# BLE232_main.net
KiCad netlist of a schematic drawn in Altium Designer
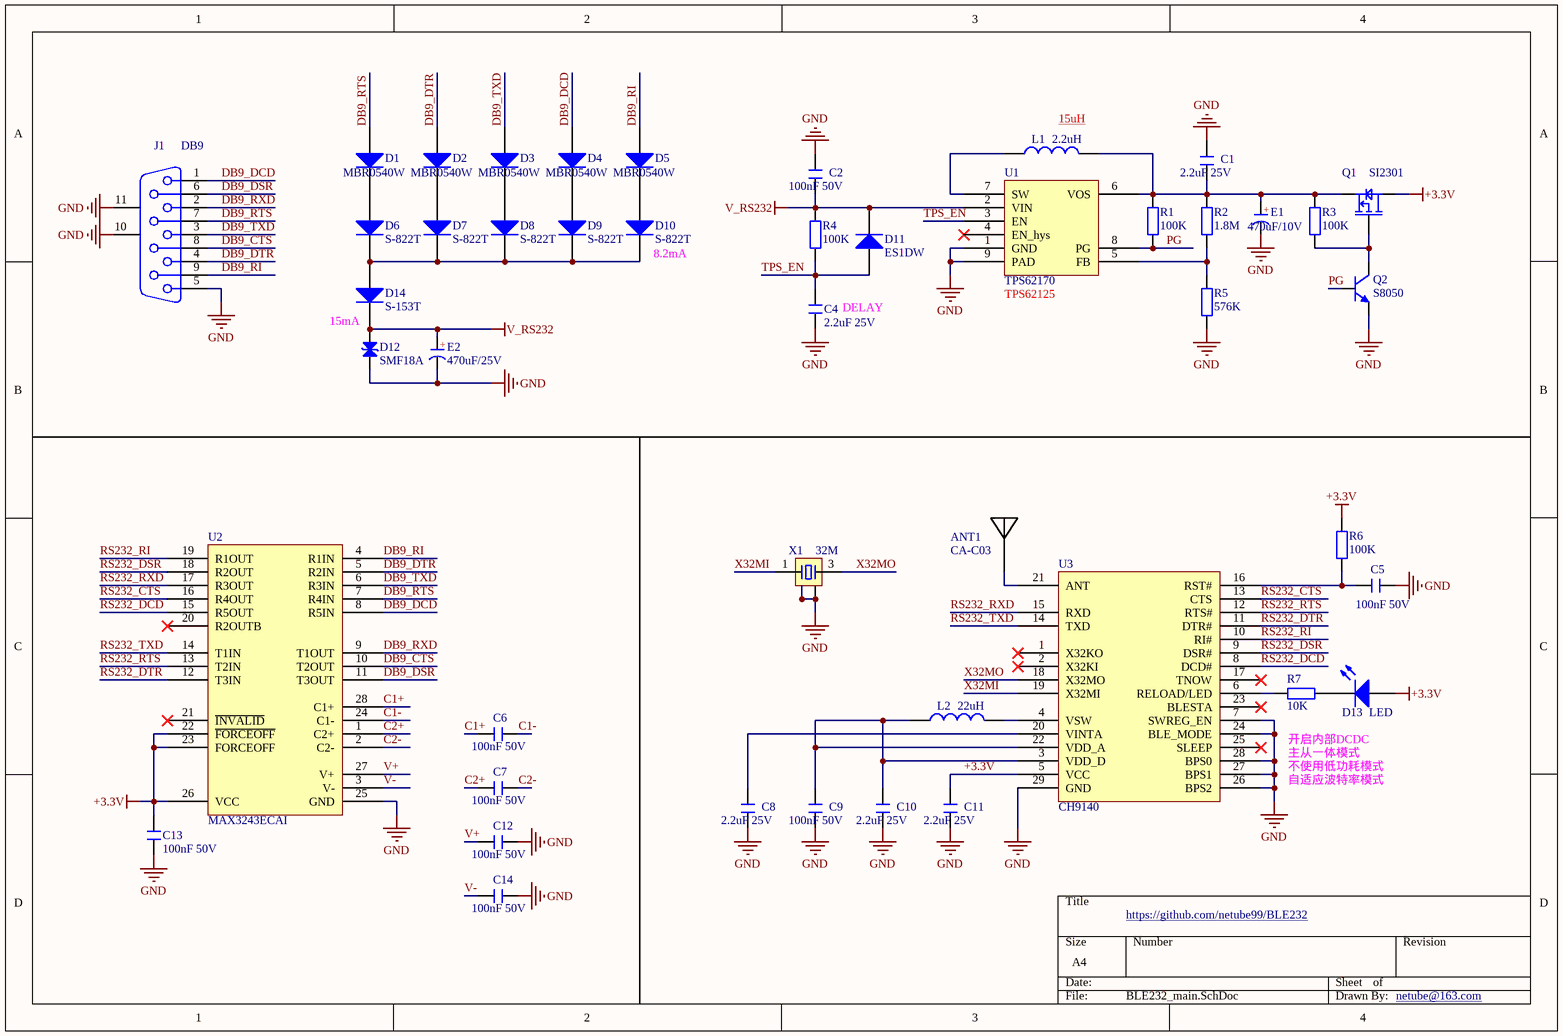
[diagram p0: BLE232_main.SchDoc]

(export (version "E")
  (design (tool "Eeschema 10.0.6"))
  (components
    (comp (ref "ANT1")
      (value "CA-C03")
      (footprint "CA-C03")
      (description "PCB板载天线")
      (fields (field (name "版权归属") "封装库来自淘宝 ID：黄晶宝石"))
      (libsource (lib "1.8 - WiFi天线-SMA射频座") (part "ANT1"))
    )
    (comp (ref "C1")
      (value "2.2uF 25V")
      (footprint "C 0603_L")
      (description "贴片电容")
      (libsource (lib "0.1 - 电阻-电容-电感") (part "C"))
    )
    (comp (ref "C2")
      (value "100nF 50V")
      (footprint "C 0603_L")
      (description "贴片电容")
      (libsource (lib "0.1 - 电阻-电容-电感") (part "C"))
    )
    (comp (ref "C4")
      (value "2.2uF 25V")
      (footprint "C 0603_L")
      (description "贴片电容")
      (libsource (lib "0.1 - 电阻-电容-电感") (part "C"))
    )
    (comp (ref "C5")
      (value "100nF 50V")
      (footprint "C 0603_L")
      (description "贴片电容")
      (libsource (lib "0.1 - 电阻-电容-电感") (part "C"))
    )
    (comp (ref "C6")
      (value "100nF 50V")
      (footprint "C 0603_L")
      (description "贴片电容")
      (libsource (lib "0.1 - 电阻-电容-电感") (part "C"))
    )
    (comp (ref "C7")
      (value "100nF 50V")
      (footprint "C 0603_L")
      (description "贴片电容")
      (libsource (lib "0.1 - 电阻-电容-电感") (part "C"))
    )
    (comp (ref "C8")
      (value "2.2uF 25V")
      (footprint "C 0603_L")
      (description "贴片电容")
      (libsource (lib "0.1 - 电阻-电容-电感") (part "C"))
    )
    (comp (ref "C9")
      (value "100nF 50V")
      (footprint "C 0603_L")
      (description "贴片电容")
      (libsource (lib "0.1 - 电阻-电容-电感") (part "C"))
    )
    (comp (ref "C10")
      (value "2.2uF 25V")
      (footprint "C 0603_L")
      (description "贴片电容")
      (libsource (lib "0.1 - 电阻-电容-电感") (part "C"))
    )
    (comp (ref "C11")
      (value "2.2uF 25V")
      (footprint "C 0603_L")
      (description "贴片电容")
      (libsource (lib "0.1 - 电阻-电容-电感") (part "C"))
    )
    (comp (ref "C12")
      (value "100nF 50V")
      (footprint "C 0603_L")
      (description "贴片电容")
      (libsource (lib "0.1 - 电阻-电容-电感") (part "C"))
    )
    (comp (ref "C13")
      (value "100nF 50V")
      (footprint "C 0603_L")
      (description "贴片电容")
      (libsource (lib "0.1 - 电阻-电容-电感") (part "C"))
    )
    (comp (ref "C14")
      (value "100nF 50V")
      (footprint "C 0603_L")
      (description "贴片电容")
      (libsource (lib "0.1 - 电阻-电容-电感") (part "C"))
    )
    (comp (ref "D1")
      (value "MBR0540W")
      (footprint "SOD-123")
      (description "二极管")
      (libsource (lib "0.2 - 二极管-整流桥") (part "Diode"))
    )
    (comp (ref "D2")
      (value "MBR0540W")
      (footprint "SOD-123")
      (description "二极管")
      (libsource (lib "0.2 - 二极管-整流桥") (part "Diode"))
    )
    (comp (ref "D3")
      (value "MBR0540W")
      (footprint "SOD-123")
      (description "二极管")
      (libsource (lib "0.2 - 二极管-整流桥") (part "Diode"))
    )
    (comp (ref "D4")
      (value "MBR0540W")
      (footprint "SOD-123")
      (description "二极管")
      (libsource (lib "0.2 - 二极管-整流桥") (part "Diode"))
    )
    (comp (ref "D5")
      (value "MBR0540W")
      (footprint "SOD-123")
      (description "二极管")
      (libsource (lib "0.2 - 二极管-整流桥") (part "Diode"))
    )
    (comp (ref "D6")
      (value "S-822T")
      (footprint "SOD-123")
      (description "二极管")
      (libsource (lib "0.2 - 二极管-整流桥") (part "Diode"))
    )
    (comp (ref "D7")
      (value "S-822T")
      (footprint "SOD-123")
      (description "二极管")
      (libsource (lib "0.2 - 二极管-整流桥") (part "Diode"))
    )
    (comp (ref "D8")
      (value "S-822T")
      (footprint "SOD-123")
      (description "二极管")
      (libsource (lib "0.2 - 二极管-整流桥") (part "Diode"))
    )
    (comp (ref "D9")
      (value "S-822T")
      (footprint "SOD-123")
      (description "二极管")
      (libsource (lib "0.2 - 二极管-整流桥") (part "Diode"))
    )
    (comp (ref "D10")
      (value "S-822T")
      (footprint "SOD-123")
      (description "二极管")
      (libsource (lib "0.2 - 二极管-整流桥") (part "Diode"))
    )
    (comp (ref "D11")
      (value "ES1DW")
      (footprint "SOD-123")
      (description "二极管")
      (libsource (lib "0.2 - 二极管-整流桥") (part "Diode"))
    )
    (comp (ref "D12")
      (value "SMF18A")
      (footprint "SOD-123")
      (description "TVS保护")
      (libsource (lib "0.2 - 二极管-整流桥") (part "TVS"))
    )
    (comp (ref "D13")
      (value "LED")
      (footprint "R 0603_L")
      (description "发光二极管")
      (libsource (lib "0.3 - LED发光二极管") (part "LED"))
    )
    (comp (ref "D14")
      (value "S-153T")
      (footprint "SOD-123")
      (description "二极管")
      (libsource (lib "0.2 - 二极管-整流桥") (part "Diode"))
    )
    (comp (ref "E1")
      (value "470uF/10V")
      (footprint "CS 2.5*6.3*7 - R")
      (description "直插固态电容")
      (libsource (lib "0.1 - 电阻-电容-电感") (part "CS"))
    )
    (comp (ref "E2")
      (value "470uF/25V")
      (footprint "CS 3.5*8*11.5 - R")
      (description "直插固态电容")
      (libsource (lib "0.1 - 电阻-电容-电感") (part "CS"))
    )
    (comp (ref "J1")
      (value "DB9")
      (footprint "DB9/S_A")
      (description "9针串口")
      (libsource (lib "0.8 - 以太网-音频-USB插座") (part "DB9"))
    )
    (comp (ref "L1")
      (value "2.2uH")
      (footprint "NLV25T")
      (description "小功率贴片电感")
      (libsource (lib "0.1 - 电阻-电容-电感") (part "L"))
    )
    (comp (ref "L2")
      (value "22uH")
      (footprint "NLV25T")
      (description "小功率贴片电感")
      (libsource (lib "0.1 - 电阻-电容-电感") (part "L"))
    )
    (comp (ref "Q1")
      (value "SI2301")
      (footprint "SOT23-3N")
      (description "P沟道场效应管")
      (libsource (lib "0.4 - 三极管-场效应管-可控硅") (part "SI2301"))
    )
    (comp (ref "Q2")
      (value "S8050")
      (footprint "SOT23-3N")
      (description "高频放大-NPN型")
      (libsource (lib "0.4 - 三极管-场效应管-可控硅") (part "8050-SMD"))
    )
    (comp (ref "R1")
      (value "100K")
      (footprint "R 0603_L")
      (description "贴片电阻")
      (libsource (lib "0.1 - 电阻-电容-电感") (part "R"))
    )
    (comp (ref "R2")
      (value "1.8M")
      (footprint "R 0603_L")
      (description "贴片电阻")
      (libsource (lib "0.1 - 电阻-电容-电感") (part "R"))
    )
    (comp (ref "R3")
      (value "100K")
      (footprint "R 0603_L")
      (description "贴片电阻")
      (libsource (lib "0.1 - 电阻-电容-电感") (part "R"))
    )
    (comp (ref "R4")
      (value "100K")
      (footprint "R 0603_L")
      (description "贴片电阻")
      (libsource (lib "0.1 - 电阻-电容-电感") (part "R"))
    )
    (comp (ref "R5")
      (value "576K")
      (footprint "R 0603_L")
      (description "贴片电阻")
      (libsource (lib "0.1 - 电阻-电容-电感") (part "R"))
    )
    (comp (ref "R6")
      (value "100K")
      (footprint "R 0603_L")
      (description "贴片电阻")
      (libsource (lib "0.1 - 电阻-电容-电感") (part "R"))
    )
    (comp (ref "R7")
      (value "10K")
      (footprint "R 0603_L")
      (description "贴片电阻")
      (libsource (lib "0.1 - 电阻-电容-电感") (part "R"))
    )
    (comp (ref "U1")
      (value "TPS62170")
      (footprint "WSON-8_2X2")
      (libsource (lib "1.1 - 电源类芯片") (part "TPS62125"))
    )
    (comp (ref "U2")
      (value "MAX3243ECAI")
      (footprint "SSOP28_N")
      (libsource (lib "1.7 - MAX系列芯片") (part "MAX3243ECAI"))
    )
    (comp (ref "U3")
      (value "CH9140")
      (footprint "QFN28 4*4")
      (libsource (lib "1.9 - CH340系列编程器芯片") (part "CH9140"))
    )
    (comp (ref "X1")
      (value "32M")
      (footprint "OSC 1612-4P")
      (description "4脚无源晶振")
      (fields (field (name "版权归属") "封装库来自淘宝卖家 ID：黄晶宝石"))
      (libsource (lib "0.5 - 保险丝-晶振-光耦") (part "XTAL-4P"))
    )
  )
  (nets
    (net (code "1") (name "+3.3V") (class "Default")
      (node (ref "C11") (pin "1") (pinfunction "1_1") (pintype "passive"))
      (node (ref "C13") (pin "1") (pinfunction "1_1") (pintype "passive"))
      (node (ref "D13") (pin "1") (pinfunction "A_1") (pintype "passive"))
      (node (ref "Q1") (pin "3") (pinfunction "D_3") (pintype "passive"))
      (node (ref "R6") (pin "2") (pinfunction "2_2") (pintype "passive"))
      (node (ref "U2") (pin "22") (pinfunction "~{FORCEOFF}_22") (pintype "passive"))
      (node (ref "U2") (pin "23") (pinfunction "FORCEOFF_23") (pintype "passive"))
      (node (ref "U2") (pin "26") (pinfunction "VCC_26") (pintype "passive"))
      (node (ref "U3") (pin "5") (pinfunction "VCC_5") (pintype "passive"))
    )
    (net (code "2") (name "/C1+") (class "Default")
      (node (ref "C6") (pin "2") (pinfunction "2_2") (pintype "passive"))
      (node (ref "U2") (pin "28") (pinfunction "C1+_28") (pintype "passive"))
    )
    (net (code "3") (name "/C1-") (class "Default")
      (node (ref "C6") (pin "1") (pinfunction "1_1") (pintype "passive"))
      (node (ref "U2") (pin "24") (pinfunction "C1-_24") (pintype "passive"))
    )
    (net (code "4") (name "/C2+") (class "Default")
      (node (ref "C7") (pin "2") (pinfunction "2_2") (pintype "passive"))
      (node (ref "U2") (pin "1") (pinfunction "C2+_1") (pintype "passive"))
    )
    (net (code "5") (name "/C2-") (class "Default")
      (node (ref "C7") (pin "1") (pinfunction "1_1") (pintype "passive"))
      (node (ref "U2") (pin "2") (pinfunction "C2-_2") (pintype "passive"))
    )
    (net (code "6") (name "/DB9_CTS") (class "Default")
      (node (ref "J1") (pin "8") (pinfunction "8_8") (pintype "passive"))
      (node (ref "U2") (pin "10") (pinfunction "T2OUT_10") (pintype "passive"))
    )
    (net (code "7") (name "/DB9_DCD") (class "Default")
      (node (ref "D4") (pin "1") (pinfunction "A_1") (pintype "passive"))
      (node (ref "J1") (pin "1") (pinfunction "1_1") (pintype "passive"))
      (node (ref "U2") (pin "8") (pinfunction "R5IN_8") (pintype "passive"))
    )
    (net (code "8") (name "/DB9_DSR") (class "Default")
      (node (ref "J1") (pin "6") (pinfunction "6_6") (pintype "passive"))
      (node (ref "U2") (pin "11") (pinfunction "T3OUT_11") (pintype "passive"))
    )
    (net (code "9") (name "/DB9_DTR") (class "Default")
      (node (ref "D2") (pin "1") (pinfunction "A_1") (pintype "passive"))
      (node (ref "J1") (pin "4") (pinfunction "4_4") (pintype "passive"))
      (node (ref "U2") (pin "5") (pinfunction "R2IN_5") (pintype "passive"))
    )
    (net (code "10") (name "/DB9_RI") (class "Default")
      (node (ref "D5") (pin "1") (pinfunction "A_1") (pintype "passive"))
      (node (ref "J1") (pin "9") (pinfunction "9_9") (pintype "passive"))
      (node (ref "U2") (pin "4") (pinfunction "R1IN_4") (pintype "passive"))
    )
    (net (code "11") (name "/DB9_RTS") (class "Default")
      (node (ref "D1") (pin "1") (pinfunction "A_1") (pintype "passive"))
      (node (ref "J1") (pin "7") (pinfunction "7_7") (pintype "passive"))
      (node (ref "U2") (pin "7") (pinfunction "R4IN_7") (pintype "passive"))
    )
    (net (code "12") (name "/DB9_RXD") (class "Default")
      (node (ref "J1") (pin "2") (pinfunction "2_2") (pintype "passive"))
      (node (ref "U2") (pin "9") (pinfunction "T1OUT_9") (pintype "passive"))
    )
    (net (code "13") (name "/DB9_TXD") (class "Default")
      (node (ref "D3") (pin "1") (pinfunction "A_1") (pintype "passive"))
      (node (ref "J1") (pin "3") (pinfunction "3_3") (pintype "passive"))
      (node (ref "U2") (pin "6") (pinfunction "R3IN_6") (pintype "passive"))
    )
    (net (code "14") (name "/PG") (class "Default")
      (node (ref "Q2") (pin "1") (pinfunction "B_1") (pintype "passive"))
      (node (ref "R1") (pin "1") (pinfunction "1_1") (pintype "passive"))
      (node (ref "U1") (pin "8") (pinfunction "PG_8") (pintype "passive"))
    )
    (net (code "15") (name "/RS232_CTS") (class "Default")
      (node (ref "U2") (pin "16") (pinfunction "R4OUT_16") (pintype "passive"))
      (node (ref "U3") (pin "13") (pinfunction "CTS_13") (pintype "passive"))
    )
    (net (code "16") (name "/RS232_DCD") (class "Default")
      (node (ref "U2") (pin "15") (pinfunction "R5OUT_15") (pintype "passive"))
      (node (ref "U3") (pin "8") (pinfunction "DCD#_8") (pintype "passive"))
    )
    (net (code "17") (name "/RS232_DSR") (class "Default")
      (node (ref "U2") (pin "18") (pinfunction "R2OUT_18") (pintype "passive"))
      (node (ref "U3") (pin "9") (pinfunction "DSR#_9") (pintype "passive"))
    )
    (net (code "18") (name "/RS232_DTR") (class "Default")
      (node (ref "U2") (pin "12") (pinfunction "T3IN_12") (pintype "passive"))
      (node (ref "U3") (pin "11") (pinfunction "DTR#_11") (pintype "passive"))
    )
    (net (code "19") (name "/RS232_RI") (class "Default")
      (node (ref "U2") (pin "19") (pinfunction "R1OUT_19") (pintype "passive"))
      (node (ref "U3") (pin "10") (pinfunction "RI#_10") (pintype "passive"))
    )
    (net (code "20") (name "/RS232_RTS") (class "Default")
      (node (ref "U2") (pin "13") (pinfunction "T2IN_13") (pintype "passive"))
      (node (ref "U3") (pin "12") (pinfunction "RTS#_12") (pintype "passive"))
    )
    (net (code "21") (name "/RS232_RXD") (class "Default")
      (node (ref "U2") (pin "17") (pinfunction "R3OUT_17") (pintype "passive"))
      (node (ref "U3") (pin "15") (pinfunction "RXD_15") (pintype "passive"))
    )
    (net (code "22") (name "/RS232_TXD") (class "Default")
      (node (ref "U2") (pin "14") (pinfunction "T1IN_14") (pintype "passive"))
      (node (ref "U3") (pin "14") (pinfunction "TXD_14") (pintype "passive"))
    )
    (net (code "23") (name "/TPS_EN") (class "Default")
      (node (ref "C4") (pin "2") (pinfunction "2_2") (pintype "passive"))
      (node (ref "D11") (pin "1") (pinfunction "A_1") (pintype "passive"))
      (node (ref "R4") (pin "1") (pinfunction "1_1") (pintype "passive"))
      (node (ref "U1") (pin "3") (pinfunction "EN_3") (pintype "passive"))
    )
    (net (code "24") (name "/V+") (class "Default")
      (node (ref "C12") (pin "2") (pinfunction "2_2") (pintype "passive"))
      (node (ref "U2") (pin "27") (pinfunction "V+_27") (pintype "passive"))
    )
    (net (code "25") (name "/V-") (class "Default")
      (node (ref "C14") (pin "2") (pinfunction "2_2") (pintype "passive"))
      (node (ref "U2") (pin "3") (pinfunction "V-_3") (pintype "passive"))
    )
    (net (code "26") (name "/X32MI") (class "Default")
      (node (ref "U3") (pin "19") (pinfunction "X32MI_19") (pintype "passive"))
      (node (ref "X1") (pin "1") (pinfunction "1_1") (pintype "passive"))
    )
    (net (code "27") (name "/X32MO") (class "Default")
      (node (ref "U3") (pin "18") (pinfunction "X32MO_18") (pintype "passive"))
      (node (ref "X1") (pin "3") (pinfunction "3_3") (pintype "passive"))
    )
    (net (code "28") (name "GND") (class "Default")
      (node (ref "C1") (pin "1") (pinfunction "1_1") (pintype "passive"))
      (node (ref "C10") (pin "2") (pinfunction "2_2") (pintype "passive"))
      (node (ref "C11") (pin "2") (pinfunction "2_2") (pintype "passive"))
      (node (ref "C12") (pin "1") (pinfunction "1_1") (pintype "passive"))
      (node (ref "C13") (pin "2") (pinfunction "2_2") (pintype "passive"))
      (node (ref "C14") (pin "1") (pinfunction "1_1") (pintype "passive"))
      (node (ref "C2") (pin "1") (pinfunction "1_1") (pintype "passive"))
      (node (ref "C4") (pin "1") (pinfunction "1_1") (pintype "passive"))
      (node (ref "C5") (pin "2") (pinfunction "2_2") (pintype "passive"))
      (node (ref "C8") (pin "2") (pinfunction "2_2") (pintype "passive"))
      (node (ref "C9") (pin "2") (pinfunction "2_2") (pintype "passive"))
      (node (ref "D12") (pin "1") (pinfunction "A_1") (pintype "passive"))
      (node (ref "E1") (pin "2") (pinfunction "K_2") (pintype "passive"))
      (node (ref "E2") (pin "2") (pinfunction "K_2") (pintype "passive"))
      (node (ref "J1") (pin "10") (pinfunction "MH1_10") (pintype "passive"))
      (node (ref "J1") (pin "11") (pinfunction "MH2_11") (pintype "passive"))
      (node (ref "J1") (pin "5") (pinfunction "5_5") (pintype "passive"))
      (node (ref "Q2") (pin "2") (pinfunction "E_2") (pintype "passive"))
      (node (ref "R5") (pin "1") (pinfunction "1_1") (pintype "passive"))
      (node (ref "U1") (pin "1") (pinfunction "GND_1") (pintype "passive"))
      (node (ref "U1") (pin "9") (pinfunction "PAD_9") (pintype "passive"))
      (node (ref "U2") (pin "25") (pinfunction "GND_25") (pintype "passive"))
      (node (ref "U3") (pin "24") (pinfunction "BLE_MODE_24") (pintype "passive"))
      (node (ref "U3") (pin "26") (pinfunction "BPS2_26") (pintype "passive"))
      (node (ref "U3") (pin "27") (pinfunction "BPS1_27") (pintype "passive"))
      (node (ref "U3") (pin "28") (pinfunction "BPS0_28") (pintype "passive"))
      (node (ref "U3") (pin "29") (pinfunction "GND_29") (pintype "passive"))
      (node (ref "U3") (pin "7") (pinfunction "SWREG_EN_7") (pintype "passive"))
      (node (ref "X1") (pin "2") (pinfunction "2_2") (pintype "passive"))
      (node (ref "X1") (pin "4") (pinfunction "4_4") (pintype "passive"))
    )
    (net (code "29") (name "Net-(D1-K)") (class "Default")
      (node (ref "D1") (pin "2") (pinfunction "K_2") (pintype "passive"))
      (node (ref "D6") (pin "1") (pinfunction "A_1") (pintype "passive"))
    )
    (net (code "30") (name "Net-(D2-K)") (class "Default")
      (node (ref "D2") (pin "2") (pinfunction "K_2") (pintype "passive"))
      (node (ref "D7") (pin "1") (pinfunction "A_1") (pintype "passive"))
    )
    (net (code "31") (name "Net-(D3-K)") (class "Default")
      (node (ref "D3") (pin "2") (pinfunction "K_2") (pintype "passive"))
      (node (ref "D8") (pin "1") (pinfunction "A_1") (pintype "passive"))
    )
    (net (code "32") (name "Net-(D4-K)") (class "Default")
      (node (ref "D4") (pin "2") (pinfunction "K_2") (pintype "passive"))
      (node (ref "D9") (pin "1") (pinfunction "A_1") (pintype "passive"))
    )
    (net (code "33") (name "Net-(D10-A)") (class "Default")
      (node (ref "D10") (pin "1") (pinfunction "A_1") (pintype "passive"))
      (node (ref "D5") (pin "2") (pinfunction "K_2") (pintype "passive"))
    )
    (net (code "34") (name "Net-(D10-K)") (class "Default")
      (node (ref "D10") (pin "2") (pinfunction "K_2") (pintype "passive"))
      (node (ref "D14") (pin "1") (pinfunction "A_1") (pintype "passive"))
      (node (ref "D6") (pin "2") (pinfunction "K_2") (pintype "passive"))
      (node (ref "D7") (pin "2") (pinfunction "K_2") (pintype "passive"))
      (node (ref "D8") (pin "2") (pinfunction "K_2") (pintype "passive"))
      (node (ref "D9") (pin "2") (pinfunction "K_2") (pintype "passive"))
    )
    (net (code "35") (name "Net-(D13-K)") (class "Default")
      (node (ref "D13") (pin "2") (pinfunction "K_2") (pintype "passive"))
      (node (ref "R7") (pin "2") (pinfunction "2_2") (pintype "passive"))
    )
    (net (code "36") (name "Net-(E1-A)") (class "Default")
      (node (ref "C1") (pin "2") (pinfunction "2_2") (pintype "passive"))
      (node (ref "E1") (pin "1") (pinfunction "A_1") (pintype "passive"))
      (node (ref "L1") (pin "2") (pinfunction "2_2") (pintype "passive"))
      (node (ref "Q1") (pin "2") (pinfunction "S_2") (pintype "passive"))
      (node (ref "R1") (pin "2") (pinfunction "2_2") (pintype "passive"))
      (node (ref "R2") (pin "2") (pinfunction "2_2") (pintype "passive"))
      (node (ref "R3") (pin "2") (pinfunction "2_2") (pintype "passive"))
      (node (ref "U1") (pin "6") (pinfunction "VOS_6") (pintype "passive"))
    )
    (net (code "37") (name "Net-(Q1-G)") (class "Default")
      (node (ref "Q1") (pin "1") (pinfunction "G_1") (pintype "passive"))
      (node (ref "Q2") (pin "3") (pinfunction "C_3") (pintype "passive"))
      (node (ref "R3") (pin "1") (pinfunction "1_1") (pintype "passive"))
    )
    (net (code "38") (name "Net-(U1-FB)") (class "Default")
      (node (ref "R2") (pin "1") (pinfunction "1_1") (pintype "passive"))
      (node (ref "R5") (pin "2") (pinfunction "2_2") (pintype "passive"))
      (node (ref "U1") (pin "5") (pinfunction "FB_5") (pintype "passive"))
    )
    (net (code "39") (name "Net-(U1-SW)") (class "Default")
      (node (ref "L1") (pin "1") (pinfunction "1_1") (pintype "passive"))
      (node (ref "U1") (pin "7") (pinfunction "SW_7") (pintype "passive"))
    )
    (net (code "40") (name "Net-(U3-ANT)") (class "Default")
      (node (ref "ANT1") (pin "1") (pinfunction "1_1") (pintype "passive"))
      (node (ref "U3") (pin "21") (pinfunction "ANT_21") (pintype "passive"))
    )
    (net (code "41") (name "Net-(U3-RELOAD{slash}LED)") (class "Default")
      (node (ref "R7") (pin "1") (pinfunction "1_1") (pintype "passive"))
      (node (ref "U3") (pin "6") (pinfunction "RELOAD/LED_6") (pintype "passive"))
    )
    (net (code "42") (name "Net-(U3-RST#)") (class "Default")
      (node (ref "C5") (pin "1") (pinfunction "1_1") (pintype "passive"))
      (node (ref "R6") (pin "1") (pinfunction "1_1") (pintype "passive"))
      (node (ref "U3") (pin "16") (pinfunction "RST#_16") (pintype "passive"))
    )
    (net (code "43") (name "Net-(U3-VDD_A)") (class "Default")
      (node (ref "C10") (pin "1") (pinfunction "1_1") (pintype "passive"))
      (node (ref "C9") (pin "1") (pinfunction "1_1") (pintype "passive"))
      (node (ref "L2") (pin "1") (pinfunction "1_1") (pintype "passive"))
      (node (ref "U3") (pin "22") (pinfunction "VDD_A_22") (pintype "passive"))
      (node (ref "U3") (pin "3") (pinfunction "VDD_D_3") (pintype "passive"))
    )
    (net (code "44") (name "Net-(U3-VINTA)") (class "Default")
      (node (ref "C8") (pin "1") (pinfunction "1_1") (pintype "passive"))
      (node (ref "U3") (pin "20") (pinfunction "VINTA_20") (pintype "passive"))
    )
    (net (code "45") (name "Net-(U3-VSW)") (class "Default")
      (node (ref "L2") (pin "2") (pinfunction "2_2") (pintype "passive"))
      (node (ref "U3") (pin "4") (pinfunction "VSW_4") (pintype "passive"))
    )
    (net (code "46") (name "V_RS232") (class "Default")
      (node (ref "C2") (pin "2") (pinfunction "2_2") (pintype "passive"))
      (node (ref "D11") (pin "2") (pinfunction "K_2") (pintype "passive"))
      (node (ref "D12") (pin "2") (pinfunction "K_2") (pintype "passive"))
      (node (ref "D14") (pin "2") (pinfunction "K_2") (pintype "passive"))
      (node (ref "E2") (pin "1") (pinfunction "A_1") (pintype "passive"))
      (node (ref "R4") (pin "2") (pinfunction "2_2") (pintype "passive"))
      (node (ref "U1") (pin "2") (pinfunction "VIN_2") (pintype "passive"))
    )
    (net (code "47") (name "unconnected-(U1-EN_hys-Pad4)") (class "Default")
      (node (ref "U1") (pin "4") (pinfunction "EN_hys_4") (pintype "passive+no_connect"))
    )
    (net (code "48") (name "unconnected-(U2-R2OUTB-Pad20)") (class "Default")
      (node (ref "U2") (pin "20") (pinfunction "R2OUTB_20") (pintype "passive+no_connect"))
    )
    (net (code "49") (name "unconnected-(U2-~{INVALID}-Pad21)") (class "Default")
      (node (ref "U2") (pin "21") (pinfunction "~{INVALID}_21") (pintype "passive+no_connect"))
    )
    (net (code "50") (name "unconnected-(U3-BLESTA-Pad23)") (class "Default")
      (node (ref "U3") (pin "23") (pinfunction "BLESTA_23") (pintype "passive+no_connect"))
    )
    (net (code "51") (name "unconnected-(U3-SLEEP-Pad25)") (class "Default")
      (node (ref "U3") (pin "25") (pinfunction "SLEEP_25") (pintype "passive+no_connect"))
    )
    (net (code "52") (name "unconnected-(U3-TNOW-Pad17)") (class "Default")
      (node (ref "U3") (pin "17") (pinfunction "TNOW_17") (pintype "passive+no_connect"))
    )
    (net (code "53") (name "unconnected-(U3-X32KI-Pad2)") (class "Default")
      (node (ref "U3") (pin "2") (pinfunction "X32KI_2") (pintype "passive+no_connect"))
    )
    (net (code "54") (name "unconnected-(U3-X32KO-Pad1)") (class "Default")
      (node (ref "U3") (pin "1") (pinfunction "X32KO_1") (pintype "passive+no_connect"))
    )
  )
)
